# Synth.net
KiCad netlist of a schematic drawn in Altium Designer
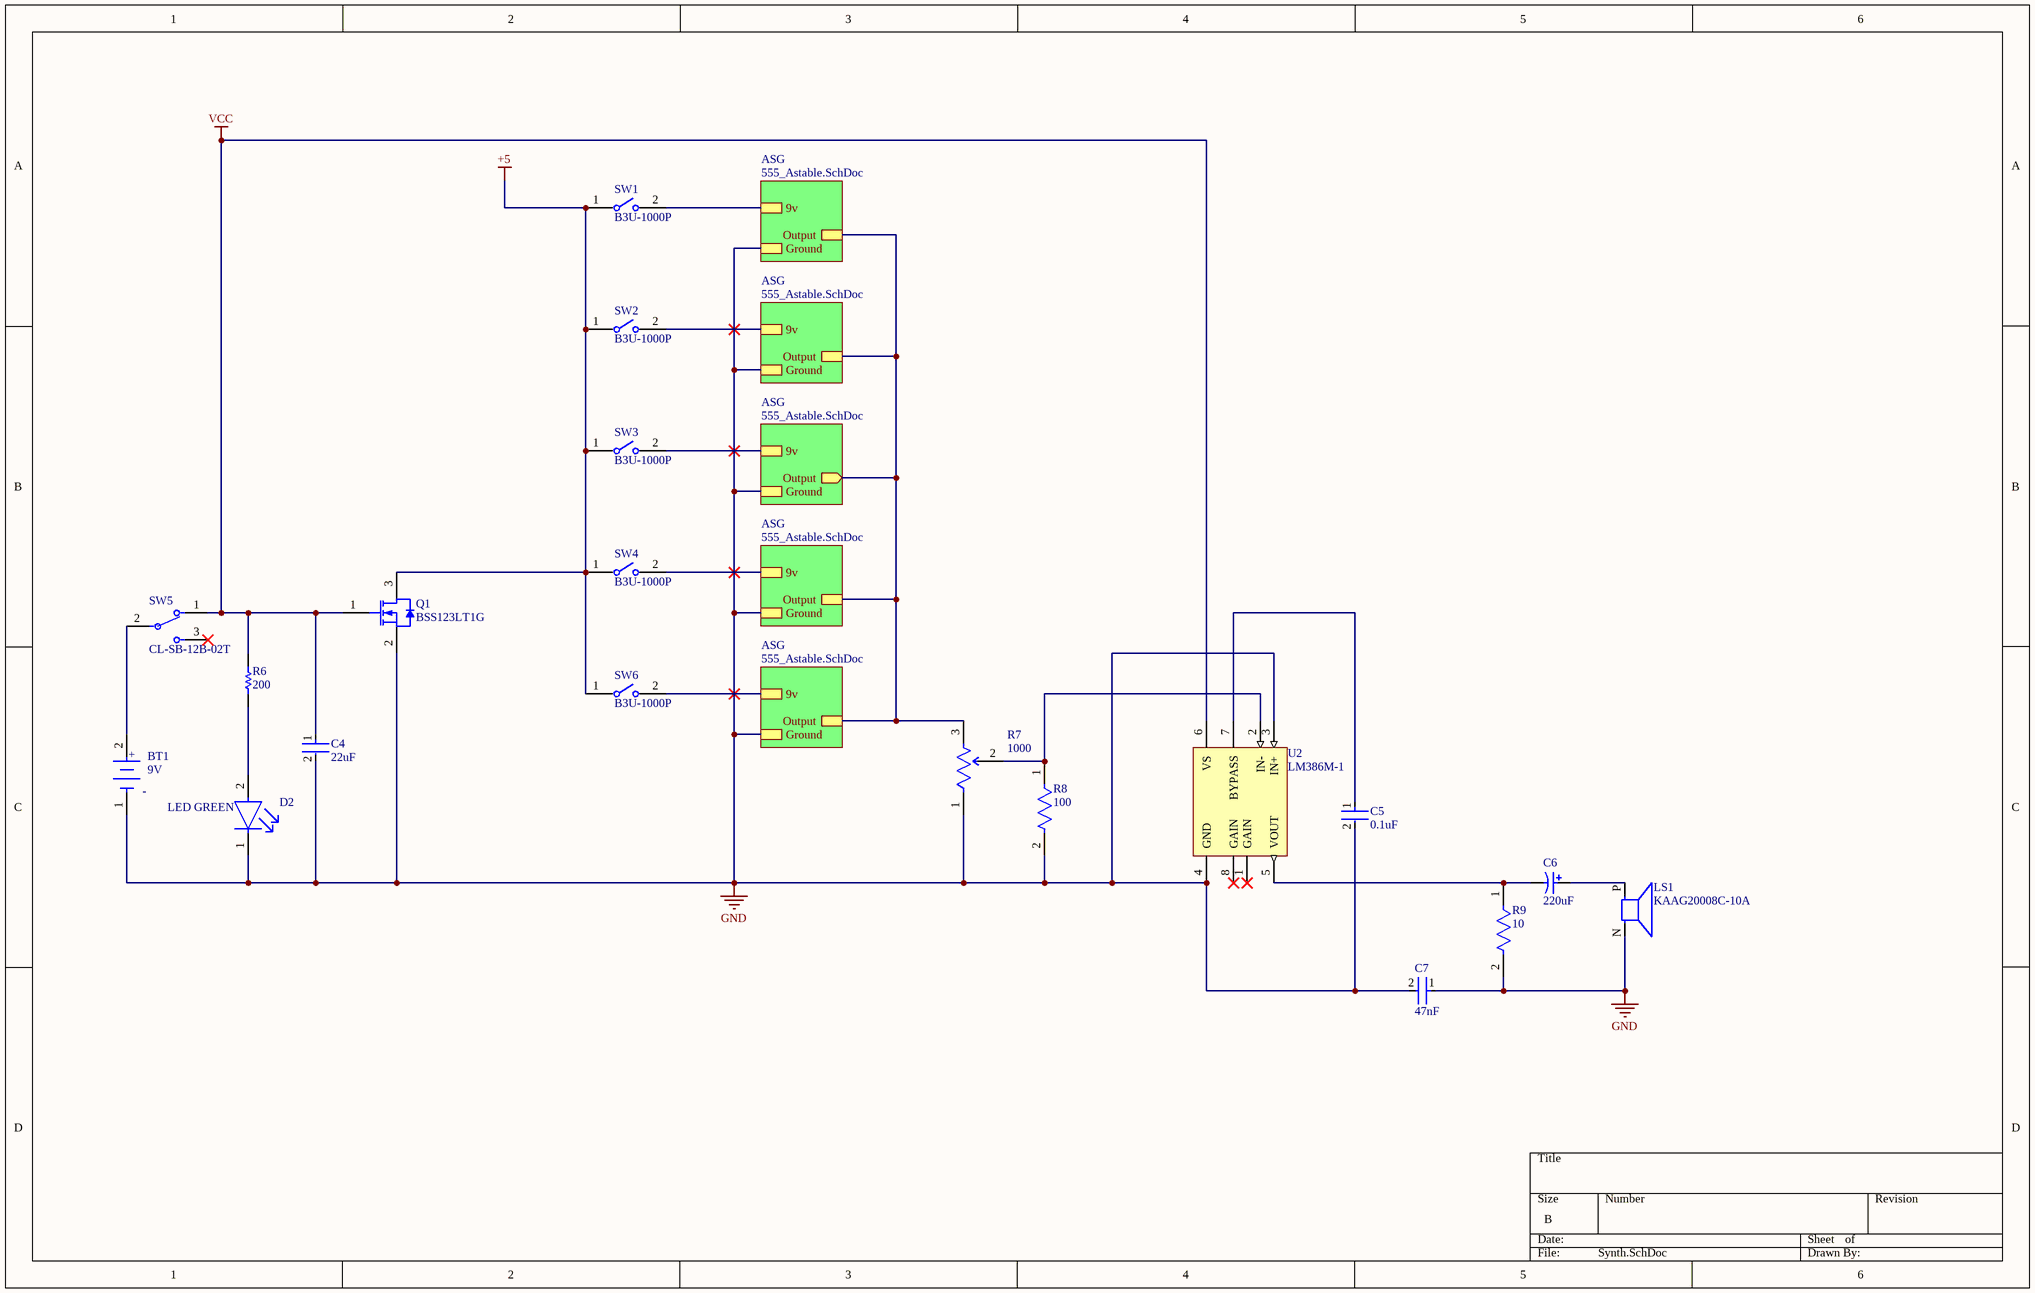
[diagram p0: Synth.SchDoc]

(export (version "E")
  (design (tool "Eeschema 10.0.6"))
  (components
    (comp (ref "BT1")
      (value "9V")
      (footprint "FP-BH9VPC-MFG")
      (description "Battery Holder (Open) 9V 1 Cell PC Pin")
      (fields (field (name "OCTOPART") "https://octopart.com/bh9vpc-memory+protection+devices-22788154"))
      (libsource (lib "Altium Content Vault") (part "60d3b5b901a8747834971d0eb8cf3fd"))
    )
    (comp (ref "C4")
      (value "22uF")
      (footprint "FP-GRM21B-0_15-MFG")
      (fields (field (name "VOLTAGE") "6.3V") (field (name "TOLERANCE") "20%"))
      (libsource (lib "Altium Content Vault") (part "b4654b650e69147ec39a6b967a45e02"))
    )
    (comp (ref "C5")
      (value "0.1uF")
      (footprint "FP-C1206C-EB-MFG")
      (description "CAP CER 0.1UF 200V 10% X7R 1206 C1206C104K2RACTU")
      (fields (field (name "TOLERANCE") "0.1") (field (name "MANUFACTURER PART NUMBER") "C1206C104K2RACTU"))
      (libsource (lib "Altium Content Vault") (part "b4654b650e69147ec39a6b967a45e02"))
    )
    (comp (ref "C6")
      (value "220uF")
      (footprint "PNSC-EEE-FK1E221P_N")
      (fields (field (name "MANUFACTURER") "Panasonic"))
      (libsource (lib "Altium Content Vault") (part "CAP-P-2"))
    )
    (comp (ref "C7")
      (value "47nF")
      (footprint "FP-C0603C-CF-MFG")
      (description "C0603 47,000 pF X7R 30ppm/°C 10.00% 50 V")
      (fields (field (name "TOLERANCE") "0.1"))
      (libsource (lib "Altium Content Vault") (part "b4654b650e69147ec39a6b967a45e02"))
    )
    (comp (ref "D2")
      (value "LED GREEN")
      (footprint "FP-LTST-C190GKT-MFG")
      (description "LED GREEN CLEAR CHIP SMDLTST-C190GKT")
      (fields (field (name "VOLTAGE") "2V"))
      (libsource (lib "Altium Content Vault") (part "8706943c75ba83719d021d2fdc84c58"))
    )
    (comp (ref "LS1")
      (value "KAAG20008C-10A")
      (footprint "SPKR_KAAG20008C-10A")
      (description "High SPL Micro Speaker, 20mm, 1W, 88dB, 1400Hz")
      (fields (field (name "MF") "Kingstate"))
      (libsource (lib "KAAG20008C-10A") (part "KAAG20008C-10A"))
    )
    (comp (ref "Q1")
      (value "BSS123LT1G")
      (footprint "ONSC-SOT-23-3-318-08_V")
      (description "Power MOSFET, 170 mA, 100 V, N-Channel, 3-Pin SOT-23, Pb-Free, Tape and Reel")
      (fields (field (name "MANUFACTURER") "On Semiconductor"))
      (libsource (lib "Altium Content Vault") (part "ONSC-NMOS-G1S2D3-3"))
    )
    (comp (ref "R6")
      (value "200")
      (footprint "RESC3216X60X45ML10T20")
      (description "CRCW1206220RFKEA")
      (fields (field (name "MANUFACTURER") "Vishay Dale"))
      (libsource (lib "Altium Content Vault") (part "RES"))
    )
    (comp (ref "R7")
      (value "1000")
      (footprint "FP-3362P-1-102TLF-MFG")
      (description "TRIMMER 1K OHM 0.5W PC PIN TOP 3362P-1-102TLF")
      (fields (field (name "TOLERANCE") "10%"))
      (libsource (lib "Altium Content Vault") (part "2dcfd2547301a7d3209a5e99acfd772"))
    )
    (comp (ref "R8")
      (value "100")
      (footprint "FP-ERJ1GN-MFG")
      (description "RES SMD 100 OHM 1% 1/20W 0201ERJ-1GNF1000C")
      (fields
        (field (name "MANUFACTURER") "Panasonic Electronic Components")
        (field (name "OCTOPART") "https://octopart.com/erj-1gnf1000c-panasonic-55419695")
      )
      (libsource (lib "Altium Content Vault") (part "1029c3af85768c4190bb7ad29bc67b5"))
    )
    (comp (ref "R9")
      (value "10")
      (footprint "FP-ERJ2RK-MFG")
      (description "RES SMD 10 OHM 1% 1/10W 0402 ERJ-2RKF10R0X")
      (fields
        (field (name "OCTOPART") "https://octopart.com/erj-2rkf10r0x-panasonic-55404982")
        (field (name "MANUFACTURER") "Panasonic")
      )
      (libsource (lib "Altium Content Vault") (part "1029c3af85768c4190bb7ad29bc67b5"))
    )
    (comp (ref "SW1")
      (value "B3U-1000P")
      (footprint "FP-B3U-1000P-MFG")
      (description "SWITCH TACTILE SPST-NO 0.05A 12V")
      (libsource (lib "Altium Content Vault") (part "ae622034201233ca1abcedc05908f33"))
    )
    (comp (ref "SW2")
      (value "B3U-1000P")
      (footprint "FP-B3U-1000P-MFG")
      (description "SWITCH TACTILE SPST-NO 0.05A 12V")
      (libsource (lib "Altium Content Vault") (part "ae622034201233ca1abcedc05908f33"))
    )
    (comp (ref "SW3")
      (value "B3U-1000P")
      (footprint "FP-B3U-1000P-MFG")
      (description "SWITCH TACTILE SPST-NO 0.05A 12V")
      (libsource (lib "Altium Content Vault") (part "ae622034201233ca1abcedc05908f33"))
    )
    (comp (ref "SW4")
      (value "B3U-1000P")
      (footprint "FP-B3U-1000P-MFG")
      (description "SWITCH TACTILE SPST-NO 0.05A 12V")
      (libsource (lib "Altium Content Vault") (part "ae622034201233ca1abcedc05908f33"))
    )
    (comp (ref "SW5")
      (value "CL-SB-12B-02T")
      (footprint "FP-CL-SB-12B-02T-MFG")
      (description "SWITCH SLIDE SPDT 200MA 12V")
      (libsource (lib "Altium Content Vault") (part "39e195cbbadc85d1df0d7eb6847d379"))
    )
    (comp (ref "SW6")
      (value "B3U-1000P")
      (footprint "FP-B3U-1000P-MFG")
      (description "SWITCH TACTILE SPST-NO 0.05A 12V")
      (libsource (lib "Altium Content Vault") (part "ae622034201233ca1abcedc05908f33"))
    )
    (comp (ref "U2")
      (value "LM386M-1")
      (footprint "D0008A_M")
      (description "Low Voltage Audio Power Amplifier, 8-pin Narrow SOIC")
      (fields (field (name "MANUFACTURER") "Texas Instruments"))
      (libsource (lib "Altium Content Vault") (part "AMP-APA-LM386-8"))
    )
  )
  (nets
    (net (code "1") (name "+5") (class "Default")
      (node (ref "Q1") (pin "3") (pinfunction "D_3") (pintype "passive"))
      (node (ref "SW1") (pin "1") (pinfunction "1_1") (pintype "passive"))
      (node (ref "SW2") (pin "1") (pinfunction "1_1") (pintype "passive"))
      (node (ref "SW3") (pin "1") (pinfunction "1_1") (pintype "passive"))
      (node (ref "SW4") (pin "1") (pinfunction "1_1") (pintype "passive"))
      (node (ref "SW6") (pin "1") (pinfunction "1_1") (pintype "passive"))
    )
    (net (code "2") (name "/9v") (class "Default")
      (node (ref "SW1") (pin "2") (pinfunction "2_2") (pintype "passive"))
    )
    (net (code "3") (name "/9v_1") (class "Default")
      (node (ref "SW3") (pin "2") (pinfunction "2_2") (pintype "passive"))
    )
    (net (code "4") (name "/9v_2") (class "Default")
      (node (ref "SW4") (pin "2") (pinfunction "2_2") (pintype "passive"))
    )
    (net (code "5") (name "/9v_3") (class "Default")
      (node (ref "SW6") (pin "2") (pinfunction "2_2") (pintype "passive"))
    )
    (net (code "6") (name "/9v_4") (class "Default")
      (node (ref "SW2") (pin "2") (pinfunction "2_2") (pintype "passive"))
    )
    (net (code "7") (name "/Output") (class "Default")
      (node (ref "R7") (pin "3") (pinfunction "CW_3") (pintype "passive"))
    )
    (net (code "8") (name "GND") (class "Default")
      (node (ref "BT1") (pin "1") (pinfunction "C_1") (pintype "passive"))
      (node (ref "C4") (pin "2") (pinfunction "2_2") (pintype "passive"))
      (node (ref "C5") (pin "2") (pinfunction "2_2") (pintype "passive"))
      (node (ref "C7") (pin "1") (pinfunction "1_1") (pintype "passive"))
      (node (ref "C7") (pin "2") (pinfunction "2_2") (pintype "passive"))
      (node (ref "D2") (pin "1") (pinfunction "C_1") (pintype "passive"))
      (node (ref "LS1") (pin "N") (pinfunction "NEG_N") (pintype "passive"))
      (node (ref "Q1") (pin "2") (pinfunction "S_2") (pintype "passive"))
      (node (ref "R7") (pin "1") (pinfunction "CCW_1") (pintype "passive"))
      (node (ref "R8") (pin "2") (pinfunction "2_2") (pintype "passive"))
      (node (ref "R9") (pin "2") (pinfunction "2_2") (pintype "passive"))
      (node (ref "U2") (pin "3") (pinfunction "IN+_3") (pintype "input"))
      (node (ref "U2") (pin "4") (pinfunction "GND_4") (pintype "power_in"))
    )
    (net (code "9") (name "Net-(BT1-A)") (class "Default")
      (node (ref "BT1") (pin "2") (pinfunction "A_2") (pintype "passive"))
      (node (ref "SW5") (pin "2") (pinfunction "C_2") (pintype "passive"))
    )
    (net (code "10") (name "Net-(D2-A)") (class "Default")
      (node (ref "D2") (pin "2") (pinfunction "A_2") (pintype "passive"))
      (node (ref "R6") (pin "1") (pinfunction "1_1") (pintype "passive"))
    )
    (net (code "11") (name "Net-(LS1-POS)") (class "Default")
      (node (ref "C6") (pin "1") (pinfunction "1_1") (pintype "passive"))
      (node (ref "LS1") (pin "P") (pinfunction "POS_P") (pintype "passive"))
    )
    (net (code "12") (name "Net-(R7-WIPER)") (class "Default")
      (node (ref "R7") (pin "2") (pinfunction "WIPER_2") (pintype "passive"))
      (node (ref "R8") (pin "1") (pinfunction "1_1") (pintype "passive"))
      (node (ref "U2") (pin "2") (pinfunction "IN-_2") (pintype "input"))
    )
    (net (code "13") (name "Net-(U2-BYPASS)") (class "Default")
      (node (ref "C5") (pin "1") (pinfunction "1_1") (pintype "passive"))
      (node (ref "U2") (pin "7") (pinfunction "BYPASS_7") (pintype "passive"))
    )
    (net (code "14") (name "Net-(U2-VOUT)") (class "Default")
      (node (ref "C6") (pin "2") (pinfunction "2_2") (pintype "passive"))
      (node (ref "R9") (pin "1") (pinfunction "1_1") (pintype "passive"))
      (node (ref "U2") (pin "5") (pinfunction "VOUT_5") (pintype "output"))
    )
    (net (code "15") (name "VCC") (class "Default")
      (node (ref "C4") (pin "1") (pinfunction "1_1") (pintype "passive"))
      (node (ref "Q1") (pin "1") (pinfunction "G_1") (pintype "passive"))
      (node (ref "R6") (pin "2") (pinfunction "2_2") (pintype "passive"))
      (node (ref "SW5") (pin "1") (pinfunction "1_1") (pintype "passive"))
      (node (ref "U2") (pin "6") (pinfunction "VS_6") (pintype "power_in"))
    )
    (net (code "16") (name "unconnected-(SW5-Pad3)") (class "Default")
      (node (ref "SW5") (pin "3") (pinfunction "3_3") (pintype "passive+no_connect"))
    )
    (net (code "17") (name "unconnected-(U2-GAIN-Pad1)") (class "Default")
      (node (ref "U2") (pin "1") (pinfunction "GAIN_1") (pintype "passive+no_connect"))
    )
    (net (code "18") (name "unconnected-(U2-GAIN-Pad8)") (class "Default")
      (node (ref "U2") (pin "8") (pinfunction "GAIN_8") (pintype "passive+no_connect"))
    )
  )
)
